# Bluetooth_CSR1010.net
KiCad netlist of a schematic drawn in Altium Designer
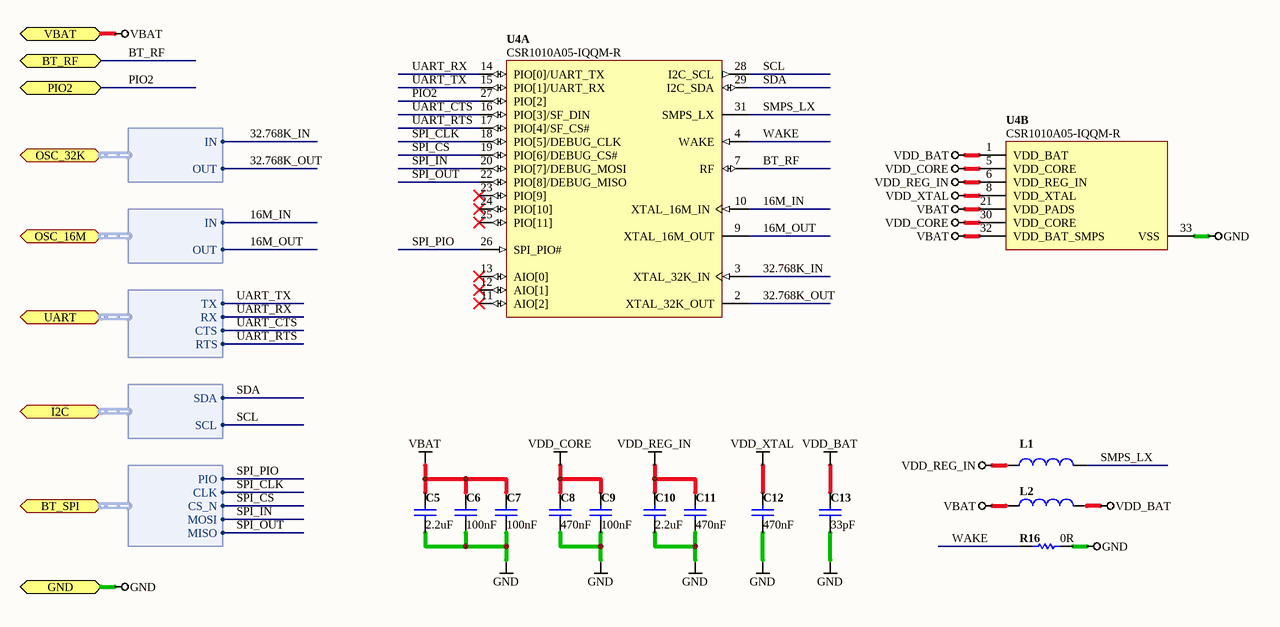
[diagram p0: Bluetooth_CSR1010.SchDoc]

(export (version "E")
  (design (tool "Eeschema 10.0.6"))
  (components
    (comp (ref "C5")
      (value "2.2uF")
      (footprint "CAPC0402(1005)60_N")
      (description "CAP 2.2uF 6.3V ±10% 0402 (1005 Metric) Thickness 0.6mm SMD")
      (fields (field (name "TOLERANCE") "±10%") (field (name "Comment") "CAP 2.2uF 6.3V 0402(1005)"))
      (libsource (lib "Altium Content Vault") (part "CMP-1034-02125-1"))
    )
    (comp (ref "C6")
      (value "100nF")
      (footprint "CAPC0402(1005)60_N")
      (description "CAP 100nF 6.3V ±5% 0402 (1005 Metric) Thickness 0.6mm SMD")
      (fields (field (name "TOLERANCE") "±5%") (field (name "Comment") "CAP 100nF 6.3V 0402(1005)"))
      (libsource (lib "Altium Content Vault") (part "CMP-1034-02060-1"))
    )
    (comp (ref "C7")
      (value "100nF")
      (footprint "CAPC0402(1005)60_N")
      (description "CAP 100nF 6.3V ±5% 0402 (1005 Metric) Thickness 0.6mm SMD")
      (fields (field (name "TOLERANCE") "±5%") (field (name "Comment") "CAP 100nF 6.3V 0402(1005)"))
      (libsource (lib "Altium Content Vault") (part "CMP-1034-02060-1"))
    )
    (comp (ref "C8")
      (value "470nF")
      (footprint "CAPC0402(1005)60_N")
      (description "CAP 470nF 6.3V ±10% 0402 (1005 Metric) Thickness 0.6mm SMD")
      (fields (field (name "TOLERANCE") "±10%") (field (name "Comment") "CAP 470nF 6.3V 0402(1005)"))
      (libsource (lib "Altium Content Vault") (part "CMP-1034-02103-1"))
    )
    (comp (ref "C9")
      (value "100nF")
      (footprint "CAPC0402(1005)60_N")
      (description "CAP 100nF 6.3V ±5% 0402 (1005 Metric) Thickness 0.6mm SMD")
      (fields (field (name "TOLERANCE") "±5%") (field (name "Comment") "CAP 100nF 6.3V 0402(1005)"))
      (libsource (lib "Altium Content Vault") (part "CMP-1034-02060-1"))
    )
    (comp (ref "C10")
      (value "2.2uF")
      (footprint "CAPC0402(1005)60_N")
      (description "CAP 2.2uF 6.3V ±10% 0402 (1005 Metric) Thickness 0.6mm SMD")
      (fields (field (name "TOLERANCE") "±10%") (field (name "Comment") "CAP 2.2uF 6.3V 0402(1005)"))
      (libsource (lib "Altium Content Vault") (part "CMP-1034-02125-1"))
    )
    (comp (ref "C11")
      (value "470nF")
      (footprint "CAPC0402(1005)60_N")
      (description "CAP 470nF 6.3V ±10% 0402 (1005 Metric) Thickness 0.6mm SMD")
      (fields (field (name "TOLERANCE") "±10%") (field (name "Comment") "CAP 470nF 6.3V 0402(1005)"))
      (libsource (lib "Altium Content Vault") (part "CMP-1034-02103-1"))
    )
    (comp (ref "C12")
      (value "470nF")
      (footprint "CAPC0402(1005)60_N")
      (description "CAP 470nF 6.3V ±10% 0402 (1005 Metric) Thickness 0.6mm SMD")
      (fields (field (name "TOLERANCE") "±10%") (field (name "Comment") "CAP 470nF 6.3V 0402(1005)"))
      (libsource (lib "Altium Content Vault") (part "CMP-1034-02103-1"))
    )
    (comp (ref "C13")
      (value "33pF")
      (footprint "CAPC0402(1005)60_N")
      (description "CAP 33pF 10V ±0.5pF 0402 (1005 Metric) Thickness 0.6mm SMD")
      (fields (field (name "TOLERANCE") "±0.5pF") (field (name "Comment") "CAP 33pF 10V 0402(1005)"))
      (libsource (lib "Altium Content Vault") (part "CMP-1034-00985-1"))
    )
    (comp (ref "L1")
      (value "7447966")
      (footprint "SMD-0603")
      (description "SMD-Multilayer Inductor WE-MI, L = 4.70 µH")
      (libsource (lib "Altium Content Vault") (part "CMP-0221-00043-1"))
    )
    (comp (ref "L2")
      (value "MMZ1005Y152CT")
      (footprint "TDK-CHIP-2_V")
      (description "Chip Bead for Signal Line, 1500 ohm at 100 MHz, -55 to 125 degC, 1.0 x 1.0 x 0.5 mm SMD")
      (fields (field (name "MANUFACTURER") "TDK") (field (name "TOLERANCE") "+/- 25%"))
      (libsource (lib "Altium Content Vault") (part "CMP-0457-00001-1"))
    )
    (comp (ref "R16")
      (value "0R")
      (footprint "RESC0402(1005)_N")
      (description "Jumper 0402 (1005 Metric)")
      (fields (field (name "TOLERANCE") "None") (field (name "Comment") "Jumper 0402(1005)"))
      (libsource (lib "Altium Content Vault") (part "CMP-1011-00001-1"))
    )
    (comp (ref "U4")
      (value "CSR1010A05-IQQM-R")
      (footprint "CSR-CSR1010A05-IQQM-R-QFN32_M")
      (description "Bluetooth Low Energy Single-mode IC, 64 KB RAM and 64 KB ROM, -30 to 85 degC, 32-pin QFN")
      (fields (field (name "MANUFACTURER") "CSR"))
      (libsource (lib "Altium Content Vault") (part "CSR-CSR1010A05-IQQM-R-QFN-32"))
    )
  )
  (nets
    (net (code "5") (name "/16M_IN") (class "Default")
      (node (ref "U4") (pin "10") (pinfunction "XTAL_16M_IN_10") (pintype "input"))
    )
    (net (code "6") (name "/16M_OUT") (class "Default")
      (node (ref "U4") (pin "9") (pinfunction "XTAL_16M_OUT_9") (pintype "passive"))
    )
    (net (code "7") (name "/32.768K_IN") (class "Default")
      (node (ref "U4") (pin "3") (pinfunction "XTAL_32K_IN_3") (pintype "input"))
    )
    (net (code "8") (name "/32.768K_OUT") (class "Default")
      (node (ref "U4") (pin "2") (pinfunction "XTAL_32K_OUT_2") (pintype "passive"))
    )
    (net (code "9") (name "/BT_RF") (class "Default")
      (node (ref "U4") (pin "7") (pinfunction "RF_7") (pintype "bidirectional"))
    )
    (net (code "10") (name "/PIO2") (class "Default")
      (node (ref "U4") (pin "27") (pinfunction "PIO[2]_27") (pintype "bidirectional"))
    )
    (net (code "11") (name "/SCL") (class "Default")
      (node (ref "U4") (pin "28") (pinfunction "I2C_SCL_28") (pintype "output"))
    )
    (net (code "12") (name "/SDA") (class "Default")
      (node (ref "U4") (pin "29") (pinfunction "I2C_SDA_29") (pintype "bidirectional"))
    )
    (net (code "13") (name "/SMPS_LX") (class "Default")
      (node (ref "L1") (pin "1") (pinfunction "1_1") (pintype "passive"))
      (node (ref "U4") (pin "31") (pinfunction "SMPS_LX_31") (pintype "power_in"))
    )
    (net (code "14") (name "/SPI_CLK") (class "Default")
      (node (ref "U4") (pin "18") (pinfunction "PIO[5]/DEBUG_CLK_18") (pintype "bidirectional"))
    )
    (net (code "15") (name "/SPI_CS") (class "Default")
      (node (ref "U4") (pin "19") (pinfunction "PIO[6]/DEBUG_CS#_19") (pintype "bidirectional"))
    )
    (net (code "16") (name "/SPI_IN") (class "Default")
      (node (ref "U4") (pin "20") (pinfunction "PIO[7]/DEBUG_MOSI_20") (pintype "bidirectional"))
    )
    (net (code "17") (name "/SPI_OUT") (class "Default")
      (node (ref "U4") (pin "22") (pinfunction "PIO[8]/DEBUG_MISO_22") (pintype "bidirectional"))
    )
    (net (code "18") (name "/SPI_PIO") (class "Default")
      (node (ref "U4") (pin "26") (pinfunction "SPI_PIO#_26") (pintype "input"))
    )
    (net (code "19") (name "/UART_CTS") (class "Default")
      (node (ref "U4") (pin "16") (pinfunction "PIO[3]/SF_DIN_16") (pintype "bidirectional"))
    )
    (net (code "20") (name "/UART_RTS") (class "Default")
      (node (ref "U4") (pin "17") (pinfunction "PIO[4]/SF_CS#_17") (pintype "bidirectional"))
    )
    (net (code "21") (name "/UART_RX") (class "Default")
      (node (ref "U4") (pin "14") (pinfunction "PIO[0]/UART_TX_14") (pintype "bidirectional"))
    )
    (net (code "22") (name "/UART_TX") (class "Default")
      (node (ref "U4") (pin "15") (pinfunction "PIO[1]/UART_RX_15") (pintype "bidirectional"))
    )
    (net (code "23") (name "/WAKE") (class "Default")
      (node (ref "R16") (pin "1") (pinfunction "1_1") (pintype "passive"))
      (node (ref "U4") (pin "4") (pinfunction "WAKE_4") (pintype "input"))
    )
    (net (code "28") (name "GND") (class "Default")
      (node (ref "C10") (pin "1") (pinfunction "1_1") (pintype "passive"))
      (node (ref "C11") (pin "1") (pinfunction "1_1") (pintype "passive"))
      (node (ref "C12") (pin "1") (pinfunction "1_1") (pintype "passive"))
      (node (ref "C13") (pin "1") (pinfunction "1_1") (pintype "passive"))
      (node (ref "C5") (pin "1") (pinfunction "1_1") (pintype "passive"))
      (node (ref "C6") (pin "1") (pinfunction "1_1") (pintype "passive"))
      (node (ref "C7") (pin "1") (pinfunction "1_1") (pintype "passive"))
      (node (ref "C8") (pin "1") (pinfunction "1_1") (pintype "passive"))
      (node (ref "C9") (pin "1") (pinfunction "1_1") (pintype "passive"))
      (node (ref "R16") (pin "2") (pinfunction "2_2") (pintype "passive"))
      (node (ref "U4") (pin "33") (pinfunction "VSS_33") (pintype "power_in"))
    )
    (net (code "29") (name "VBAT") (class "Default")
      (node (ref "C5") (pin "2") (pinfunction "2_2") (pintype "passive"))
      (node (ref "C6") (pin "2") (pinfunction "2_2") (pintype "passive"))
      (node (ref "C7") (pin "2") (pinfunction "2_2") (pintype "passive"))
      (node (ref "L2") (pin "1") (pinfunction "1_1") (pintype "passive"))
      (node (ref "U4") (pin "21") (pinfunction "VDD_PADS_21") (pintype "power_in"))
      (node (ref "U4") (pin "32") (pinfunction "VDD_BAT_SMPS_32") (pintype "power_in"))
    )
    (net (code "30") (name "VDD_BAT") (class "Default")
      (node (ref "C13") (pin "2") (pinfunction "2_2") (pintype "passive"))
      (node (ref "L2") (pin "2") (pinfunction "2_2") (pintype "passive"))
      (node (ref "U4") (pin "1") (pinfunction "VDD_BAT_1") (pintype "power_in"))
    )
    (net (code "31") (name "VDD_CORE") (class "Default")
      (node (ref "C8") (pin "2") (pinfunction "2_2") (pintype "passive"))
      (node (ref "C9") (pin "2") (pinfunction "2_2") (pintype "passive"))
      (node (ref "U4") (pin "30") (pinfunction "VDD_CORE_30") (pintype "power_in"))
      (node (ref "U4") (pin "5") (pinfunction "VDD_CORE_5") (pintype "power_in"))
    )
    (net (code "32") (name "VDD_REG_IN") (class "Default")
      (node (ref "C10") (pin "2") (pinfunction "2_2") (pintype "passive"))
      (node (ref "C11") (pin "2") (pinfunction "2_2") (pintype "passive"))
      (node (ref "L1") (pin "2") (pinfunction "2_2") (pintype "passive"))
      (node (ref "U4") (pin "6") (pinfunction "VDD_REG_IN_6") (pintype "power_in"))
    )
    (net (code "33") (name "VDD_XTAL") (class "Default")
      (node (ref "C12") (pin "2") (pinfunction "2_2") (pintype "passive"))
      (node (ref "U4") (pin "8") (pinfunction "VDD_XTAL_8") (pintype "power_in"))
    )
    (net (code "34") (name "unconnected-(U4A-AIO[0]-Pad13)") (class "Default")
      (node (ref "U4") (pin "13") (pinfunction "AIO[0]_13") (pintype "bidirectional+no_connect"))
    )
    (net (code "35") (name "unconnected-(U4A-AIO[1]-Pad12)") (class "Default")
      (node (ref "U4") (pin "12") (pinfunction "AIO[1]_12") (pintype "bidirectional+no_connect"))
    )
    (net (code "36") (name "unconnected-(U4A-AIO[2]-Pad11)") (class "Default")
      (node (ref "U4") (pin "11") (pinfunction "AIO[2]_11") (pintype "bidirectional+no_connect"))
    )
    (net (code "37") (name "unconnected-(U4A-PIO[9]-Pad23)") (class "Default")
      (node (ref "U4") (pin "23") (pinfunction "PIO[9]_23") (pintype "bidirectional+no_connect"))
    )
    (net (code "38") (name "unconnected-(U4A-PIO[10]-Pad24)") (class "Default")
      (node (ref "U4") (pin "24") (pinfunction "PIO[10]_24") (pintype "bidirectional+no_connect"))
    )
    (net (code "39") (name "unconnected-(U4A-PIO[11]-Pad25)") (class "Default")
      (node (ref "U4") (pin "25") (pinfunction "PIO[11]_25") (pintype "bidirectional+no_connect"))
    )
  )
)
